# ET-GCLK.net
KiCad netlist of a schematic drawn in Altium Designer
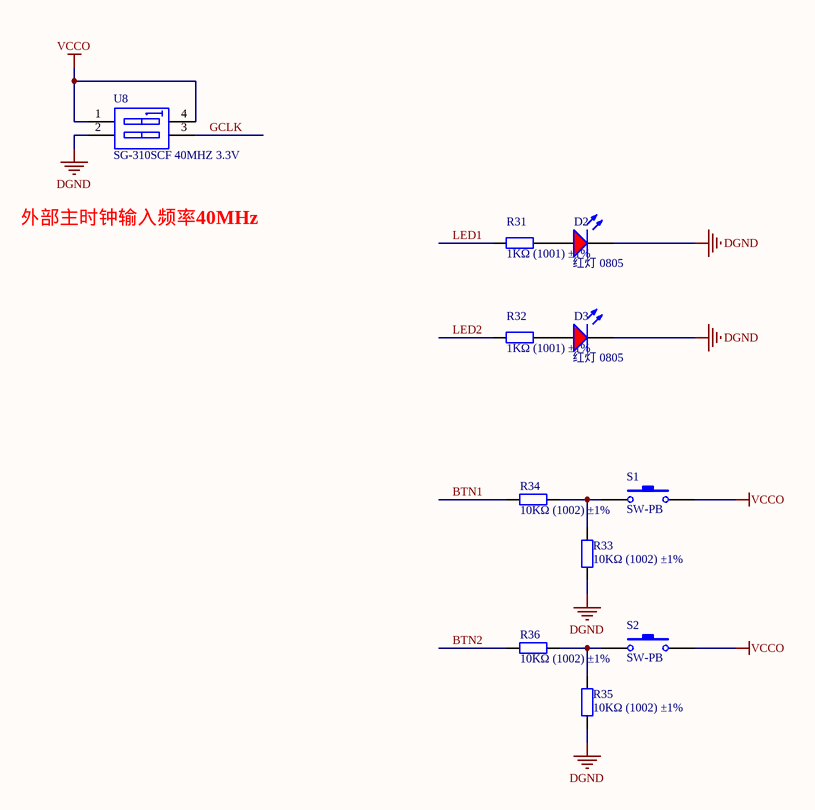
[diagram p0: ET-GCLK.SchDoc]

(export (version "E")
  (design (tool "Eeschema 10.0.6"))
  (components
    (comp (ref "D2")
      (value "红灯 0805")
      (footprint "LC-0805_LED_S1")
      (description "发光二极管")
      (libsource (lib "Miscellaneous Devices LC") (part "0805 红灯"))
    )
    (comp (ref "D3")
      (value "红灯 0805")
      (footprint "LC-0805_LED_S1")
      (description "发光二极管")
      (libsource (lib "Miscellaneous Devices LC") (part "0805 红灯"))
    )
    (comp (ref "R31")
      (value "1KΩ (1001) ±1%")
      (footprint "LC-0805_R")
      (description "贴片电阻")
      (libsource (lib "Miscellaneous Devices LC") (part "0805 1KΩ (1001) 1%"))
    )
    (comp (ref "R32")
      (value "1KΩ (1001) ±1%")
      (footprint "LC-0805_R")
      (description "贴片电阻")
      (libsource (lib "Miscellaneous Devices LC") (part "0805 1KΩ (1001) 1%"))
    )
    (comp (ref "R33")
      (value "10KΩ (1002) ±1%")
      (footprint "LC-0805_R")
      (description "贴片电阻")
      (libsource (lib "Miscellaneous Devices LC") (part "0805 10KΩ (1002) 1%"))
    )
    (comp (ref "R34")
      (value "10KΩ (1002) ±1%")
      (footprint "LC-0805_R")
      (description "贴片电阻")
      (libsource (lib "") (part "0805 10KΩ (1002) 1%_1"))
    )
    (comp (ref "R35")
      (value "10KΩ (1002) ±1%")
      (footprint "LC-0805_R")
      (description "贴片电阻")
      (libsource (lib "Miscellaneous Devices LC") (part "0805 10KΩ (1002) 1%"))
    )
    (comp (ref "R36")
      (value "10KΩ (1002) ±1%")
      (footprint "LC-0805_R")
      (description "贴片电阻")
      (libsource (lib "") (part "0805 10KΩ (1002) 1%_1"))
    )
    (comp (ref "S1")
      (value "SW-PB")
      (footprint "SPST-2")
      (description "Switch")
      (fields (field (name "PUBLISHER") "Altium Limited"))
      (libsource (lib "Miscellaneous Devices") (part "SW-PB"))
    )
    (comp (ref "S2")
      (value "SW-PB")
      (footprint "SPST-2")
      (description "Switch")
      (fields (field (name "PUBLISHER") "Altium Limited"))
      (libsource (lib "Miscellaneous Devices") (part "SW-PB"))
    )
    (comp (ref "U8")
      (value "SG-310SCF 40MHZ 3.3V")
      (footprint "LC-SMD-7050_4P")
      (description "DIP Switch, 2 Position, SPST")
      (fields (field (name "PUBLISHER") "Altium Limited"))
      (libsource (lib "Miscellaneous Devices") (part "SW DIP-2"))
    )
  )
  (nets
    (net (code "1") (name "/BTN1") (class "Default")
      (node (ref "R34") (pin "1") (pinfunction "1_1") (pintype "passive"))
    )
    (net (code "2") (name "/BTN2") (class "Default")
      (node (ref "R36") (pin "1") (pinfunction "1_1") (pintype "passive"))
    )
    (net (code "3") (name "/GCLK") (class "Default")
      (node (ref "U8") (pin "3") (pinfunction "B2_3") (pintype "passive"))
    )
    (net (code "4") (name "/LED1") (class "Default")
      (node (ref "R31") (pin "1") (pinfunction "1_1") (pintype "passive"))
    )
    (net (code "5") (name "/LED2") (class "Default")
      (node (ref "R32") (pin "1") (pinfunction "1_1") (pintype "passive"))
    )
    (net (code "6") (name "DGND") (class "Default")
      (node (ref "D2") (pin "K") (pinfunction "K_K") (pintype "passive"))
      (node (ref "D3") (pin "K") (pinfunction "K_K") (pintype "passive"))
      (node (ref "R33") (pin "1") (pinfunction "1_1") (pintype "passive"))
      (node (ref "R35") (pin "1") (pinfunction "1_1") (pintype "passive"))
      (node (ref "U8") (pin "2") (pinfunction "A2_2") (pintype "passive"))
    )
    (net (code "7") (name "Net-(D2-PadA)") (class "Default")
      (node (ref "D2") (pin "A") (pinfunction "A_A") (pintype "passive"))
      (node (ref "R31") (pin "2") (pinfunction "2_2") (pintype "passive"))
    )
    (net (code "8") (name "Net-(D3-PadA)") (class "Default")
      (node (ref "D3") (pin "A") (pinfunction "A_A") (pintype "passive"))
      (node (ref "R32") (pin "2") (pinfunction "2_2") (pintype "passive"))
    )
    (net (code "9") (name "Net-(R33-Pad2)") (class "Default")
      (node (ref "R33") (pin "2") (pinfunction "2_2") (pintype "passive"))
      (node (ref "R34") (pin "2") (pinfunction "2_2") (pintype "passive"))
      (node (ref "S1") (pin "1") (pinfunction "1_1") (pintype "passive"))
    )
    (net (code "10") (name "Net-(R35-Pad2)") (class "Default")
      (node (ref "R35") (pin "2") (pinfunction "2_2") (pintype "passive"))
      (node (ref "R36") (pin "2") (pinfunction "2_2") (pintype "passive"))
      (node (ref "S2") (pin "1") (pinfunction "1_1") (pintype "passive"))
    )
    (net (code "11") (name "VCCO") (class "Default")
      (node (ref "S1") (pin "2") (pinfunction "2_2") (pintype "passive"))
      (node (ref "S2") (pin "2") (pinfunction "2_2") (pintype "passive"))
      (node (ref "U8") (pin "1") (pinfunction "A1_1") (pintype "passive"))
      (node (ref "U8") (pin "4") (pinfunction "B1_4") (pintype "passive"))
    )
  )
)
